# BinaryWatch_v0_4_OptR_fix.net
KiCad netlist of a schematic drawn in EAGLE
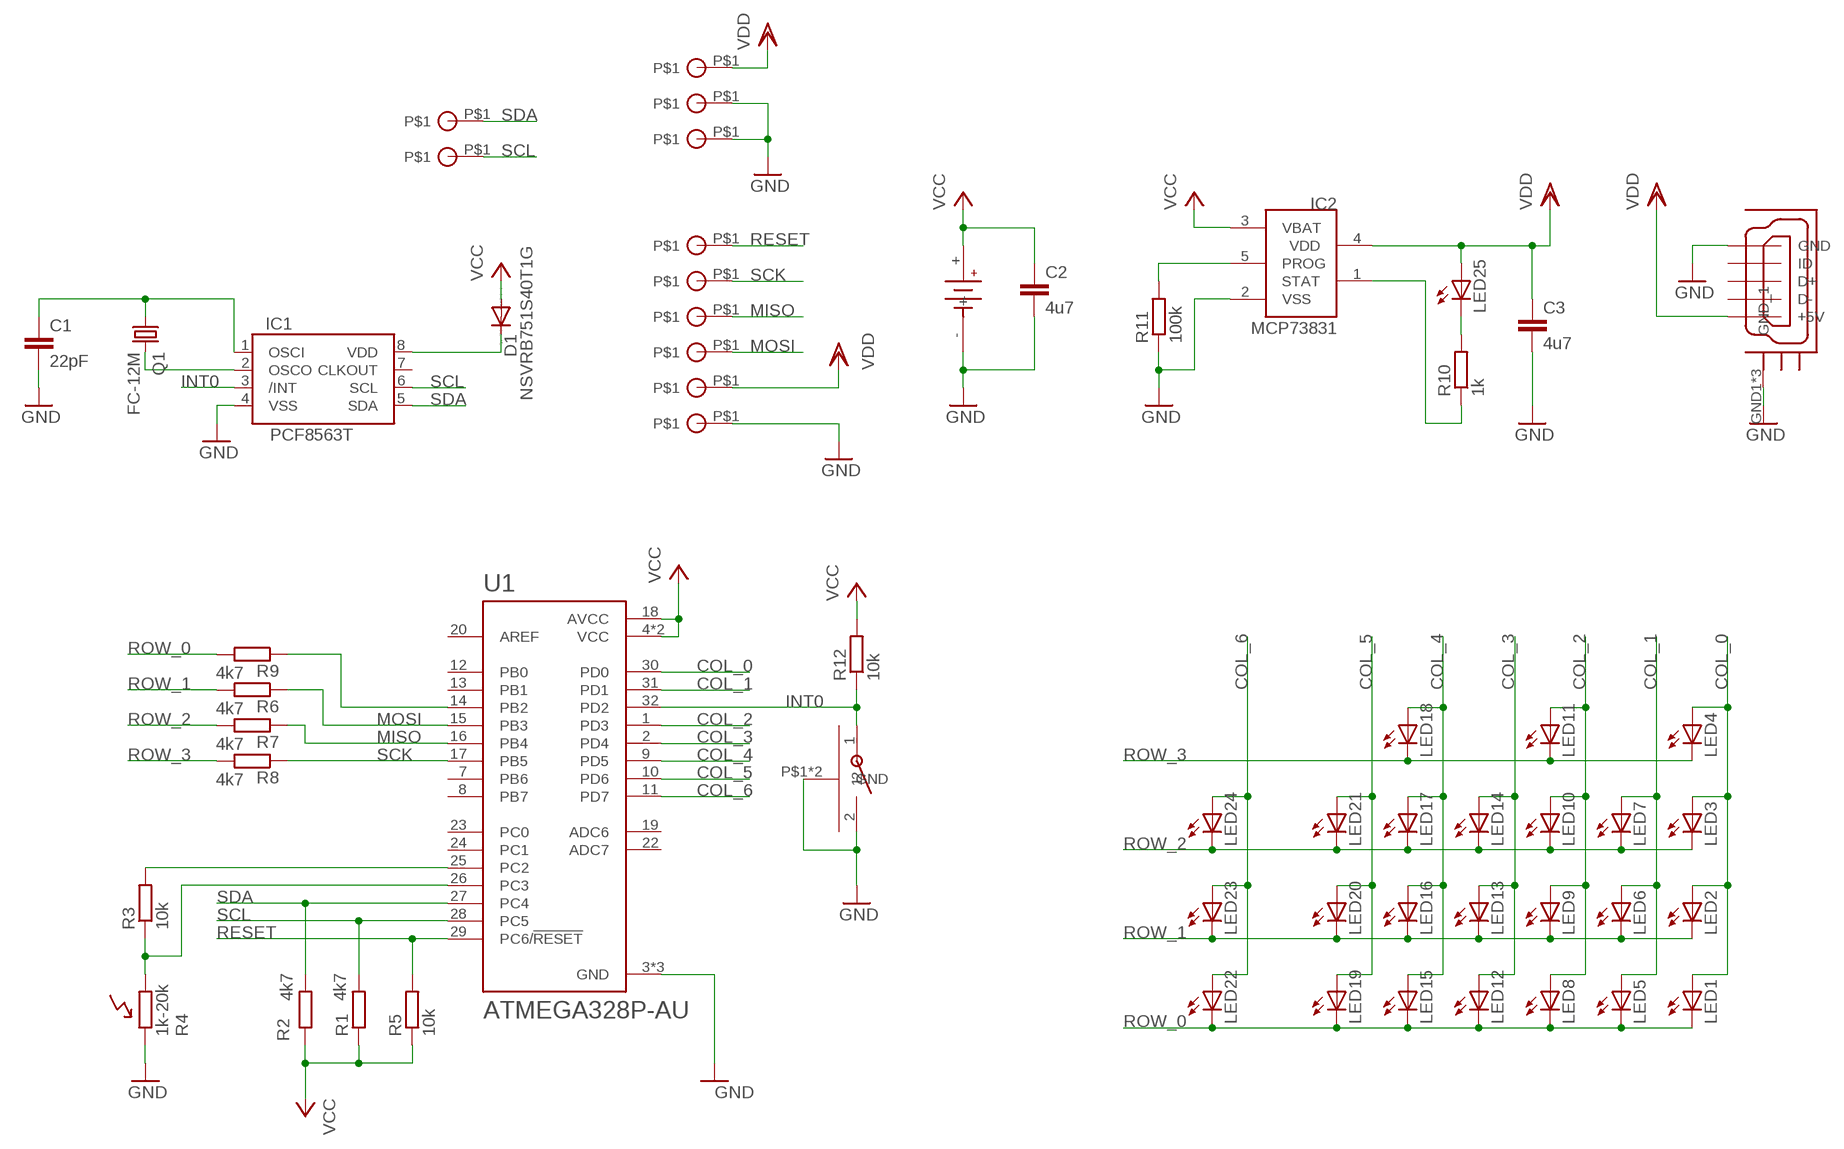
[diagram p0: schematic, sheet 1]

(export (version "E")
  (design (tool "Eeschema 10.0.6"))
  (components
    (comp (ref "C1")
      (value "22pF")
      (footprint "eagle-import:C0603")
      (libsource (lib "eagle-import") (part "C-EUC0603"))
    )
    (comp (ref "C2")
      (value "4u7")
      (footprint "eagle-import:C0603")
      (libsource (lib "eagle-import") (part "C-EUC0603"))
    )
    (comp (ref "C3")
      (value "4u7")
      (footprint "eagle-import:C0603")
      (libsource (lib "eagle-import") (part "C-EUC0603"))
    )
    (comp (ref "D1")
      (value "NSVRB751S40T1G")
      (footprint "eagle-import:SOD523")
      (libsource (lib "eagle-import") (part "DIODE-SOD523"))
    )
    (comp (ref "IC1")
      (value "PCF8563T")
      (footprint "eagle-import:SO8")
      (libsource (lib "eagle-import") (part "PCF8563T"))
    )
    (comp (ref "IC2")
      (value "MCP73831")
      (footprint "eagle-import:SOT23-5L")
      (libsource (lib "eagle-import") (part "MCP73831"))
    )
    (comp (ref "LED1")
      (value "LEDSML0603")
      (footprint "eagle-import:SML0603")
      (libsource (lib "eagle-import") (part "LEDSML0603"))
    )
    (comp (ref "LED2")
      (value "LEDSML0603")
      (footprint "eagle-import:SML0603")
      (libsource (lib "eagle-import") (part "LEDSML0603"))
    )
    (comp (ref "LED3")
      (value "LEDSML0603")
      (footprint "eagle-import:SML0603")
      (libsource (lib "eagle-import") (part "LEDSML0603"))
    )
    (comp (ref "LED4")
      (value "LEDSML0603")
      (footprint "eagle-import:SML0603")
      (libsource (lib "eagle-import") (part "LEDSML0603"))
    )
    (comp (ref "LED5")
      (value "LEDSML0603")
      (footprint "eagle-import:SML0603")
      (libsource (lib "eagle-import") (part "LEDSML0603"))
    )
    (comp (ref "LED6")
      (value "LEDSML0603")
      (footprint "eagle-import:SML0603")
      (libsource (lib "eagle-import") (part "LEDSML0603"))
    )
    (comp (ref "LED7")
      (value "LEDSML0603")
      (footprint "eagle-import:SML0603")
      (libsource (lib "eagle-import") (part "LEDSML0603"))
    )
    (comp (ref "LED8")
      (value "LEDSML0603")
      (footprint "eagle-import:SML0603")
      (libsource (lib "eagle-import") (part "LEDSML0603"))
    )
    (comp (ref "LED9")
      (value "LEDSML0603")
      (footprint "eagle-import:SML0603")
      (libsource (lib "eagle-import") (part "LEDSML0603"))
    )
    (comp (ref "LED10")
      (value "LEDSML0603")
      (footprint "eagle-import:SML0603")
      (libsource (lib "eagle-import") (part "LEDSML0603"))
    )
    (comp (ref "LED11")
      (value "LEDSML0603")
      (footprint "eagle-import:SML0603")
      (libsource (lib "eagle-import") (part "LEDSML0603"))
    )
    (comp (ref "LED12")
      (value "LEDSML0603")
      (footprint "eagle-import:SML0603")
      (libsource (lib "eagle-import") (part "LEDSML0603"))
    )
    (comp (ref "LED13")
      (value "LEDSML0603")
      (footprint "eagle-import:SML0603")
      (libsource (lib "eagle-import") (part "LEDSML0603"))
    )
    (comp (ref "LED14")
      (value "LEDSML0603")
      (footprint "eagle-import:SML0603")
      (libsource (lib "eagle-import") (part "LEDSML0603"))
    )
    (comp (ref "LED15")
      (value "LEDSML0603")
      (footprint "eagle-import:SML0603")
      (libsource (lib "eagle-import") (part "LEDSML0603"))
    )
    (comp (ref "LED16")
      (value "LEDSML0603")
      (footprint "eagle-import:SML0603")
      (libsource (lib "eagle-import") (part "LEDSML0603"))
    )
    (comp (ref "LED17")
      (value "LEDSML0603")
      (footprint "eagle-import:SML0603")
      (libsource (lib "eagle-import") (part "LEDSML0603"))
    )
    (comp (ref "LED18")
      (value "LEDSML0603")
      (footprint "eagle-import:SML0603")
      (libsource (lib "eagle-import") (part "LEDSML0603"))
    )
    (comp (ref "LED19")
      (value "LEDSML0603")
      (footprint "eagle-import:SML0603")
      (libsource (lib "eagle-import") (part "LEDSML0603"))
    )
    (comp (ref "LED20")
      (value "LEDSML0603")
      (footprint "eagle-import:SML0603")
      (libsource (lib "eagle-import") (part "LEDSML0603"))
    )
    (comp (ref "LED21")
      (value "LEDSML0603")
      (footprint "eagle-import:SML0603")
      (libsource (lib "eagle-import") (part "LEDSML0603"))
    )
    (comp (ref "LED22")
      (value "LEDSML0603")
      (footprint "eagle-import:SML0603")
      (libsource (lib "eagle-import") (part "LEDSML0603"))
    )
    (comp (ref "LED23")
      (value "LEDSML0603")
      (footprint "eagle-import:SML0603")
      (libsource (lib "eagle-import") (part "LEDSML0603"))
    )
    (comp (ref "LED24")
      (value "LEDSML0603")
      (footprint "eagle-import:SML0603")
      (libsource (lib "eagle-import") (part "LEDSML0603"))
    )
    (comp (ref "LED25")
      (value "LEDSML0603")
      (footprint "eagle-import:SML0603")
      (libsource (lib "eagle-import") (part "LEDSML0603"))
    )
    (comp (ref "Q1")
      (value "FC-12M")
      (footprint "eagle-import:FC-12M")
      (libsource (lib "eagle-import") (part "FC-12M"))
    )
    (comp (ref "R1")
      (value "4k7")
      (footprint "eagle-import:R0603")
      (libsource (lib "eagle-import") (part "resistor_R-EU_R0603"))
    )
    (comp (ref "R2")
      (value "4k7")
      (footprint "eagle-import:R0603")
      (libsource (lib "eagle-import") (part "resistor_R-EU_R0603"))
    )
    (comp (ref "R3")
      (value "10k")
      (footprint "eagle-import:R0603")
      (libsource (lib "eagle-import") (part "R-EU_R0603"))
    )
    (comp (ref "R4")
      (value "1k-20k")
      (footprint "eagle-import:OPTO_RES_ROUND_3_5MM")
      (libsource (lib "eagle-import") (part "OPTO_RES_ROUND_3_5MM"))
    )
    (comp (ref "R5")
      (value "10k")
      (footprint "eagle-import:R0603")
      (libsource (lib "eagle-import") (part "resistor_R-EU_R0603"))
    )
    (comp (ref "R6")
      (value "4k7")
      (footprint "eagle-import:R0603")
      (libsource (lib "eagle-import") (part "resistor_R-EU_R0603"))
    )
    (comp (ref "R7")
      (value "4k7")
      (footprint "eagle-import:R0603")
      (libsource (lib "eagle-import") (part "resistor_R-EU_R0603"))
    )
    (comp (ref "R8")
      (value "4k7")
      (footprint "eagle-import:R0603")
      (libsource (lib "eagle-import") (part "resistor_R-EU_R0603"))
    )
    (comp (ref "R9")
      (value "4k7")
      (footprint "eagle-import:R0603")
      (libsource (lib "eagle-import") (part "resistor_R-EU_R0603"))
    )
    (comp (ref "R10")
      (value "1k")
      (footprint "eagle-import:R0603")
      (libsource (lib "eagle-import") (part "R-EU_R0603"))
    )
    (comp (ref "R11")
      (value "100k")
      (footprint "eagle-import:R0603")
      (libsource (lib "eagle-import") (part "R-EU_R0603"))
    )
    (comp (ref "R12")
      (value "10k")
      (footprint "eagle-import:R0603")
      (libsource (lib "eagle-import") (part "rcl_334_R-EU_R0603"))
    )
    (comp (ref "U$1")
      (value "2032")
      (footprint "eagle-import:2032_45DEG")
      (libsource (lib "eagle-import") (part "2032"))
    )
    (comp (ref "U$2")
      (value "CONTACT_1_8MM")
      (footprint "eagle-import:CONTACT_1_8MM")
      (libsource (lib "eagle-import") (part "CONTACT_1_8MM"))
    )
    (comp (ref "U$3")
      (value "CONTACT_1_8MM")
      (footprint "eagle-import:CONTACT_1_8MM")
      (libsource (lib "eagle-import") (part "CONTACT_1_8MM"))
    )
    (comp (ref "U$4")
      (value "CONTACT_1_8MM")
      (footprint "eagle-import:CONTACT_1_8MM")
      (libsource (lib "eagle-import") (part "CONTACT_1_8MM"))
    )
    (comp (ref "U$5")
      (value "CONTACT_1_8MM")
      (footprint "eagle-import:CONTACT_1_8MM")
      (libsource (lib "eagle-import") (part "CONTACT_1_8MM"))
    )
    (comp (ref "U$6")
      (value "CONTACT_1_8MM")
      (footprint "eagle-import:CONTACT_1_8MM")
      (libsource (lib "eagle-import") (part "CONTACT_1_8MM"))
    )
    (comp (ref "U$7")
      (value "CONTACT_1_8MM")
      (footprint "eagle-import:CONTACT_1_8MM")
      (libsource (lib "eagle-import") (part "CONTACT_1_8MM"))
    )
    (comp (ref "U$8")
      (value "TACK_SWITCH")
      (footprint "eagle-import:TL3330")
      (libsource (lib "eagle-import") (part "TACK_SWITCH"))
    )
    (comp (ref "U$9")
      (value "CONTACT_1_8MM")
      (footprint "eagle-import:CONTACT_1_8MM")
      (libsource (lib "eagle-import") (part "CONTACT_1_8MM"))
    )
    (comp (ref "U$10")
      (value "MICRO_USB_VERTICAL")
      (footprint "eagle-import:MICRO_USB_VERTICAL")
      (libsource (lib "eagle-import") (part "MICRO_USB_VERTICAL"))
    )
    (comp (ref "U$11")
      (value "CONTACT_1_8MM")
      (footprint "eagle-import:CONTACT_1_8MM")
      (libsource (lib "eagle-import") (part "CONTACT_1_8MM"))
    )
    (comp (ref "U$12")
      (value "CONTACT_1_8MM")
      (footprint "eagle-import:CONTACT_1_8MM")
      (libsource (lib "eagle-import") (part "CONTACT_1_8MM"))
    )
    (comp (ref "U$13")
      (value "CONTACT_1_8MM")
      (footprint "eagle-import:CONTACT_1_8MM")
      (libsource (lib "eagle-import") (part "CONTACT_1_8MM"))
    )
    (comp (ref "U$14")
      (value "CONTACT_1_8MM")
      (footprint "eagle-import:CONTACT_1_8MM")
      (libsource (lib "eagle-import") (part "CONTACT_1_8MM"))
    )
    (comp (ref "U1")
      (value "ATMEGA328P-AU")
      (footprint "eagle-import:QFP80P900X900X120-32N")
      (fields (field (name "MF") "Microchip"))
      (libsource (lib "eagle-import") (part "ATMEGA328P-AU"))
    )
  )
  (nets
    (net (code "1") (name "/COL_0") (class "Default")
      (node (ref "LED1") (pin "A") (pinfunction "A_A") (pintype "passive"))
      (node (ref "LED2") (pin "A") (pinfunction "A_A") (pintype "passive"))
      (node (ref "LED3") (pin "A") (pinfunction "A_A") (pintype "passive"))
      (node (ref "LED4") (pin "A") (pinfunction "A_A") (pintype "passive"))
      (node (ref "U1") (pin "30") (pinfunction "PD0_30") (pintype "bidirectional"))
    )
    (net (code "2") (name "/COL_1") (class "Default")
      (node (ref "LED5") (pin "A") (pinfunction "A_A") (pintype "passive"))
      (node (ref "LED6") (pin "A") (pinfunction "A_A") (pintype "passive"))
      (node (ref "LED7") (pin "A") (pinfunction "A_A") (pintype "passive"))
      (node (ref "U1") (pin "31") (pinfunction "PD1_31") (pintype "bidirectional"))
    )
    (net (code "3") (name "/COL_2") (class "Default")
      (node (ref "LED10") (pin "A") (pinfunction "A_A") (pintype "passive"))
      (node (ref "LED11") (pin "A") (pinfunction "A_A") (pintype "passive"))
      (node (ref "LED8") (pin "A") (pinfunction "A_A") (pintype "passive"))
      (node (ref "LED9") (pin "A") (pinfunction "A_A") (pintype "passive"))
      (node (ref "U1") (pin "1") (pinfunction "PD3_1") (pintype "bidirectional"))
    )
    (net (code "4") (name "/COL_3") (class "Default")
      (node (ref "LED12") (pin "A") (pinfunction "A_A") (pintype "passive"))
      (node (ref "LED13") (pin "A") (pinfunction "A_A") (pintype "passive"))
      (node (ref "LED14") (pin "A") (pinfunction "A_A") (pintype "passive"))
      (node (ref "U1") (pin "2") (pinfunction "PD4_2") (pintype "bidirectional"))
    )
    (net (code "5") (name "/COL_4") (class "Default")
      (node (ref "LED15") (pin "A") (pinfunction "A_A") (pintype "passive"))
      (node (ref "LED16") (pin "A") (pinfunction "A_A") (pintype "passive"))
      (node (ref "LED17") (pin "A") (pinfunction "A_A") (pintype "passive"))
      (node (ref "LED18") (pin "A") (pinfunction "A_A") (pintype "passive"))
      (node (ref "U1") (pin "9") (pinfunction "PD5_9") (pintype "bidirectional"))
    )
    (net (code "6") (name "/COL_5") (class "Default")
      (node (ref "LED19") (pin "A") (pinfunction "A_A") (pintype "passive"))
      (node (ref "LED20") (pin "A") (pinfunction "A_A") (pintype "passive"))
      (node (ref "LED21") (pin "A") (pinfunction "A_A") (pintype "passive"))
      (node (ref "U1") (pin "10") (pinfunction "PD6_10") (pintype "bidirectional"))
    )
    (net (code "7") (name "/COL_6") (class "Default")
      (node (ref "LED22") (pin "A") (pinfunction "A_A") (pintype "passive"))
      (node (ref "LED23") (pin "A") (pinfunction "A_A") (pintype "passive"))
      (node (ref "LED24") (pin "A") (pinfunction "A_A") (pintype "passive"))
      (node (ref "U1") (pin "11") (pinfunction "PD7_11") (pintype "bidirectional"))
    )
    (net (code "8") (name "/INT0") (class "Default")
      (node (ref "IC1") (pin "3") (pinfunction "/INT_3") (pintype "bidirectional"))
      (node (ref "R12") (pin "1") (pinfunction "1_1") (pintype "passive"))
      (node (ref "U$8") (pin "1") (pinfunction "1_1") (pintype "bidirectional"))
      (node (ref "U1") (pin "32") (pinfunction "PD2_32") (pintype "bidirectional"))
    )
    (net (code "9") (name "/MISO") (class "Default")
      (node (ref "R7") (pin "1") (pinfunction "1_1") (pintype "passive"))
      (node (ref "U$5") (pin "P$1") (pinfunction "P$1_P$1") (pintype "bidirectional"))
      (node (ref "U1") (pin "16") (pinfunction "PB4_16") (pintype "bidirectional"))
    )
    (net (code "10") (name "/MOSI") (class "Default")
      (node (ref "R6") (pin "1") (pinfunction "1_1") (pintype "passive"))
      (node (ref "U$4") (pin "P$1") (pinfunction "P$1_P$1") (pintype "bidirectional"))
      (node (ref "U1") (pin "15") (pinfunction "PB3_15") (pintype "bidirectional"))
    )
    (net (code "11") (name "/RESET") (class "Default")
      (node (ref "R5") (pin "2") (pinfunction "2_2") (pintype "passive"))
      (node (ref "U$7") (pin "P$1") (pinfunction "P$1_P$1") (pintype "bidirectional"))
      (node (ref "U1") (pin "29") (pinfunction "PC6/~{RESET}_29") (pintype "bidirectional"))
    )
    (net (code "12") (name "/ROW_0") (class "Default")
      (node (ref "LED1") (pin "C") (pinfunction "C_C") (pintype "passive"))
      (node (ref "LED12") (pin "C") (pinfunction "C_C") (pintype "passive"))
      (node (ref "LED15") (pin "C") (pinfunction "C_C") (pintype "passive"))
      (node (ref "LED19") (pin "C") (pinfunction "C_C") (pintype "passive"))
      (node (ref "LED22") (pin "C") (pinfunction "C_C") (pintype "passive"))
      (node (ref "LED5") (pin "C") (pinfunction "C_C") (pintype "passive"))
      (node (ref "LED8") (pin "C") (pinfunction "C_C") (pintype "passive"))
      (node (ref "R9") (pin "2") (pinfunction "2_2") (pintype "passive"))
    )
    (net (code "13") (name "/ROW_1") (class "Default")
      (node (ref "LED13") (pin "C") (pinfunction "C_C") (pintype "passive"))
      (node (ref "LED16") (pin "C") (pinfunction "C_C") (pintype "passive"))
      (node (ref "LED2") (pin "C") (pinfunction "C_C") (pintype "passive"))
      (node (ref "LED20") (pin "C") (pinfunction "C_C") (pintype "passive"))
      (node (ref "LED23") (pin "C") (pinfunction "C_C") (pintype "passive"))
      (node (ref "LED6") (pin "C") (pinfunction "C_C") (pintype "passive"))
      (node (ref "LED9") (pin "C") (pinfunction "C_C") (pintype "passive"))
      (node (ref "R6") (pin "2") (pinfunction "2_2") (pintype "passive"))
    )
    (net (code "14") (name "/ROW_2") (class "Default")
      (node (ref "LED10") (pin "C") (pinfunction "C_C") (pintype "passive"))
      (node (ref "LED14") (pin "C") (pinfunction "C_C") (pintype "passive"))
      (node (ref "LED17") (pin "C") (pinfunction "C_C") (pintype "passive"))
      (node (ref "LED21") (pin "C") (pinfunction "C_C") (pintype "passive"))
      (node (ref "LED24") (pin "C") (pinfunction "C_C") (pintype "passive"))
      (node (ref "LED3") (pin "C") (pinfunction "C_C") (pintype "passive"))
      (node (ref "LED7") (pin "C") (pinfunction "C_C") (pintype "passive"))
      (node (ref "R7") (pin "2") (pinfunction "2_2") (pintype "passive"))
    )
    (net (code "15") (name "/ROW_3") (class "Default")
      (node (ref "LED11") (pin "C") (pinfunction "C_C") (pintype "passive"))
      (node (ref "LED18") (pin "C") (pinfunction "C_C") (pintype "passive"))
      (node (ref "LED4") (pin "C") (pinfunction "C_C") (pintype "passive"))
      (node (ref "R8") (pin "2") (pinfunction "2_2") (pintype "passive"))
    )
    (net (code "16") (name "/SCK") (class "Default")
      (node (ref "R8") (pin "1") (pinfunction "1_1") (pintype "passive"))
      (node (ref "U$6") (pin "P$1") (pinfunction "P$1_P$1") (pintype "bidirectional"))
      (node (ref "U1") (pin "17") (pinfunction "PB5_17") (pintype "bidirectional"))
    )
    (net (code "17") (name "/SCL") (class "Default")
      (node (ref "IC1") (pin "6") (pinfunction "SCL_6") (pintype "bidirectional"))
      (node (ref "R1") (pin "2") (pinfunction "2_2") (pintype "passive"))
      (node (ref "U$14") (pin "P$1") (pinfunction "P$1_P$1") (pintype "bidirectional"))
      (node (ref "U1") (pin "28") (pinfunction "PC5_28") (pintype "bidirectional"))
    )
    (net (code "18") (name "/SDA") (class "Default")
      (node (ref "IC1") (pin "5") (pinfunction "SDA_5") (pintype "bidirectional"))
      (node (ref "R2") (pin "2") (pinfunction "2_2") (pintype "passive"))
      (node (ref "U$13") (pin "P$1") (pinfunction "P$1_P$1") (pintype "bidirectional"))
      (node (ref "U1") (pin "27") (pinfunction "PC4_27") (pintype "bidirectional"))
    )
    (net (code "19") (name "GND") (class "Default")
      (node (ref "C1") (pin "2") (pinfunction "2_2") (pintype "passive"))
      (node (ref "C2") (pin "2") (pinfunction "2_2") (pintype "passive"))
      (node (ref "C3") (pin "2") (pinfunction "2_2") (pintype "passive"))
      (node (ref "IC1") (pin "4") (pinfunction "VSS_4") (pintype "bidirectional"))
      (node (ref "IC2") (pin "2") (pinfunction "VSS_2") (pintype "bidirectional"))
      (node (ref "R11") (pin "1") (pinfunction "1_1") (pintype "passive"))
      (node (ref "R4") (pin "P$1") (pinfunction "1_P$1") (pintype "passive"))
      (node (ref "U$1") (pin "-") (pinfunction "-_-") (pintype "bidirectional"))
      (node (ref "U$10") (pin "5") (pinfunction "GND_5") (pintype "passive"))
      (node (ref "U$10") (pin "GND1") (pinfunction "GND_1_GND1") (pintype "bidirectional"))
      (node (ref "U$10") (pin "GND2") (pinfunction "GND_1_GND2") (pintype "bidirectional"))
      (node (ref "U$10") (pin "GND3") (pinfunction "GND_1_GND3") (pintype "bidirectional"))
      (node (ref "U$12") (pin "P$1") (pinfunction "P$1_P$1") (pintype "bidirectional"))
      (node (ref "U$2") (pin "P$1") (pinfunction "P$1_P$1") (pintype "bidirectional"))
      (node (ref "U$8") (pin "2") (pinfunction "2_2") (pintype "bidirectional"))
      (node (ref "U$8") (pin "P$1") (pinfunction "GND_P$1") (pintype "bidirectional"))
      (node (ref "U$8") (pin "P$2") (pinfunction "GND_P$2") (pintype "bidirectional"))
      (node (ref "U$9") (pin "P$1") (pinfunction "P$1_P$1") (pintype "bidirectional"))
      (node (ref "U1") (pin "21") (pinfunction "GND_21") (pintype "power_in"))
      (node (ref "U1") (pin "3") (pinfunction "GND_3") (pintype "power_in"))
      (node (ref "U1") (pin "5") (pinfunction "GND_5") (pintype "power_in"))
    )
    (net (code "20") (name "Net-(IC1-OSCI)") (class "Default")
      (node (ref "C1") (pin "1") (pinfunction "1_1") (pintype "passive"))
      (node (ref "IC1") (pin "1") (pinfunction "OSCI_1") (pintype "bidirectional"))
      (node (ref "Q1") (pin "1") (pinfunction "1_1") (pintype "passive"))
    )
    (net (code "21") (name "Net-(IC1-OSCO)") (class "Default")
      (node (ref "IC1") (pin "2") (pinfunction "OSCO_2") (pintype "bidirectional"))
      (node (ref "Q1") (pin "2") (pinfunction "2_2") (pintype "passive"))
    )
    (net (code "22") (name "Net-(IC1-VDD)") (class "Default")
      (node (ref "D1") (pin "C") (pinfunction "C_C") (pintype "passive"))
      (node (ref "IC1") (pin "8") (pinfunction "VDD_8") (pintype "bidirectional"))
    )
    (net (code "23") (name "Net-(IC2-PROG)") (class "Default")
      (node (ref "IC2") (pin "5") (pinfunction "PROG_5") (pintype "bidirectional"))
      (node (ref "R11") (pin "2") (pinfunction "2_2") (pintype "passive"))
    )
    (net (code "24") (name "Net-(IC2-STAT)") (class "Default")
      (node (ref "IC2") (pin "1") (pinfunction "STAT_1") (pintype "bidirectional"))
      (node (ref "R10") (pin "1") (pinfunction "1_1") (pintype "passive"))
    )
    (net (code "25") (name "Net-(LED25-PadC)") (class "Default")
      (node (ref "LED25") (pin "C") (pinfunction "C_C") (pintype "passive"))
      (node (ref "R10") (pin "2") (pinfunction "2_2") (pintype "passive"))
    )
    (net (code "26") (name "Net-(R4-2)") (class "Default")
      (node (ref "R3") (pin "1") (pinfunction "1_1") (pintype "passive"))
      (node (ref "R4") (pin "P$2") (pinfunction "2_P$2") (pintype "passive"))
      (node (ref "U1") (pin "26") (pinfunction "PC3_26") (pintype "bidirectional"))
    )
    (net (code "27") (name "Net-(U1-PB2)") (class "Default")
      (node (ref "R9") (pin "1") (pinfunction "1_1") (pintype "passive"))
      (node (ref "U1") (pin "14") (pinfunction "PB2_14") (pintype "bidirectional"))
    )
    (net (code "28") (name "Net-(U1-PC2)") (class "Default")
      (node (ref "R3") (pin "2") (pinfunction "2_2") (pintype "passive"))
      (node (ref "U1") (pin "25") (pinfunction "PC2_25") (pintype "bidirectional"))
    )
    (net (code "29") (name "VCC") (class "Default")
      (node (ref "C2") (pin "1") (pinfunction "1_1") (pintype "passive"))
      (node (ref "D1") (pin "A") (pinfunction "A_A") (pintype "passive"))
      (node (ref "IC2") (pin "3") (pinfunction "VBAT_3") (pintype "bidirectional"))
      (node (ref "R1") (pin "1") (pinfunction "1_1") (pintype "passive"))
      (node (ref "R12") (pin "2") (pinfunction "2_2") (pintype "passive"))
      (node (ref "R2") (pin "1") (pinfunction "1_1") (pintype "passive"))
      (node (ref "R5") (pin "1") (pinfunction "1_1") (pintype "passive"))
      (node (ref "U$1") (pin "+") (pinfunction "+_+") (pintype "bidirectional"))
      (node (ref "U1") (pin "18") (pinfunction "AVCC_18") (pintype "power_in"))
      (node (ref "U1") (pin "4") (pinfunction "VCC_4") (pintype "power_in"))
      (node (ref "U1") (pin "6") (pinfunction "VCC_6") (pintype "power_in"))
    )
    (net (code "30") (name "VDD") (class "Default")
      (node (ref "C3") (pin "1") (pinfunction "1_1") (pintype "passive"))
      (node (ref "IC2") (pin "4") (pinfunction "VDD_4") (pintype "bidirectional"))
      (node (ref "LED25") (pin "A") (pinfunction "A_A") (pintype "passive"))
      (node (ref "U$10") (pin "1") (pinfunction "+5V_1") (pintype "passive"))
      (node (ref "U$11") (pin "P$1") (pinfunction "P$1_P$1") (pintype "bidirectional"))
      (node (ref "U$3") (pin "P$1") (pinfunction "P$1_P$1") (pintype "bidirectional"))
    )
    (net (code "31") (name "unconnected-(IC1-CLKOUT-Pad7)") (class "Default")
      (node (ref "IC1") (pin "7") (pinfunction "CLKOUT_7") (pintype "bidirectional"))
    )
    (net (code "32") (name "unconnected-(U$10-D+-Pad3)") (class "Default")
      (node (ref "U$10") (pin "3") (pinfunction "D+_3") (pintype "passive"))
    )
    (net (code "33") (name "unconnected-(U$10-D--Pad2)") (class "Default")
      (node (ref "U$10") (pin "2") (pinfunction "D-_2") (pintype "passive"))
    )
    (net (code "34") (name "unconnected-(U$10-ID-Pad4)") (class "Default")
      (node (ref "U$10") (pin "4") (pinfunction "ID_4") (pintype "passive"))
    )
    (net (code "35") (name "unconnected-(U1-ADC6-Pad19)") (class "Default")
      (node (ref "U1") (pin "19") (pinfunction "ADC6_19") (pintype "bidirectional"))
    )
    (net (code "36") (name "unconnected-(U1-ADC7-Pad22)") (class "Default")
      (node (ref "U1") (pin "22") (pinfunction "ADC7_22") (pintype "bidirectional"))
    )
    (net (code "37") (name "unconnected-(U1-AREF-Pad20)") (class "Default")
      (node (ref "U1") (pin "20") (pinfunction "AREF_20") (pintype "input"))
    )
    (net (code "38") (name "unconnected-(U1-PB0-Pad12)") (class "Default")
      (node (ref "U1") (pin "12") (pinfunction "PB0_12") (pintype "bidirectional"))
    )
    (net (code "39") (name "unconnected-(U1-PB1-Pad13)") (class "Default")
      (node (ref "U1") (pin "13") (pinfunction "PB1_13") (pintype "bidirectional"))
    )
    (net (code "40") (name "unconnected-(U1-PB6-Pad7)") (class "Default")
      (node (ref "U1") (pin "7") (pinfunction "PB6_7") (pintype "bidirectional"))
    )
    (net (code "41") (name "unconnected-(U1-PB7-Pad8)") (class "Default")
      (node (ref "U1") (pin "8") (pinfunction "PB7_8") (pintype "bidirectional"))
    )
    (net (code "42") (name "unconnected-(U1-PC0-Pad23)") (class "Default")
      (node (ref "U1") (pin "23") (pinfunction "PC0_23") (pintype "bidirectional"))
    )
    (net (code "43") (name "unconnected-(U1-PC1-Pad24)") (class "Default")
      (node (ref "U1") (pin "24") (pinfunction "PC1_24") (pintype "bidirectional"))
    )
  )
)
